# UnidadDeControl-STM.net
KiCad netlist of a schematic drawn in Altium Designer
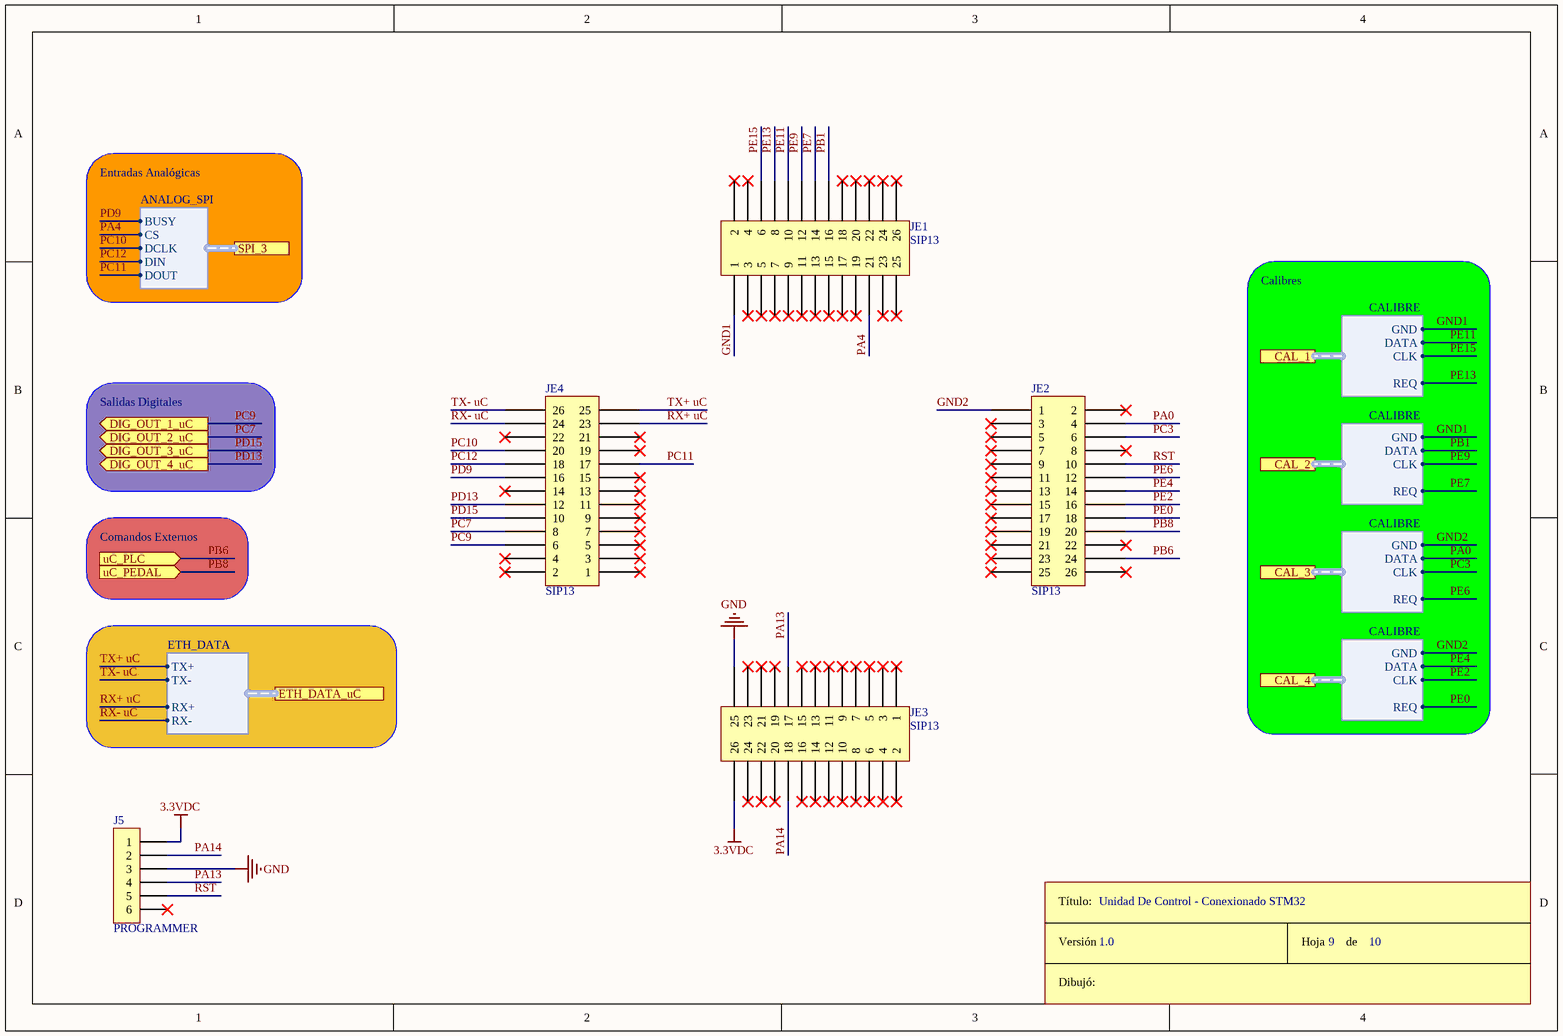
[diagram p0: UnidadDeControl-STM.SchDoc]

(export (version "E")
  (design (tool "Eeschema 10.0.6"))
  (components
    (comp (ref "J5") (value "PROGRAMMER") (footprint "SIP6") (libsource (lib "LIBEBAL") (part "CON6")))
    (comp (ref "JE1")
      (value "SIP13")
      (footprint "SIP13*2 - HDR")
      (libsource (lib "AditionalComponents") (part "CON13*2"))
    )
    (comp (ref "JE2") (value "SIP13") (footprint "SIP13*2 - HDR") (libsource (lib "") (part "CON13*2_3")))
    (comp (ref "JE3") (value "SIP13") (footprint "SIP13*2 - HDR") (libsource (lib "") (part "CON13*2_1")))
    (comp (ref "JE4") (value "SIP13") (footprint "SIP13*2 - HDR") (libsource (lib "") (part "CON13*2_2")))
    (comp (ref "ROT8") (value "Rótulo") (libsource (lib "LIB PIO IX") (part "Rótulo")))
  )
  (nets
    (net (code "4") (name "/GND1") (class "Default")
      (node (ref "JE1") (pin "1") (pinfunction "1_1") (pintype "passive"))
    )
    (net (code "5") (name "/GND2") (class "Default")
      (node (ref "JE2") (pin "1") (pinfunction "1_1") (pintype "passive"))
    )
    (net (code "6") (name "/PA0") (class "Default")
      (node (ref "JE2") (pin "4") (pinfunction "4_4") (pintype "passive"))
    )
    (net (code "7") (name "/PA4") (class "Default")
      (node (ref "JE1") (pin "21") (pinfunction "21_21") (pintype "passive"))
    )
    (net (code "8") (name "/PA13") (class "Default")
      (node (ref "J5") (pin "4") (pinfunction "4_4") (pintype "passive"))
      (node (ref "JE3") (pin "17") (pinfunction "17_17") (pintype "passive"))
    )
    (net (code "9") (name "/PA14") (class "Default")
      (node (ref "J5") (pin "2") (pinfunction "2_2") (pintype "passive"))
      (node (ref "JE3") (pin "18") (pinfunction "18_18") (pintype "passive"))
    )
    (net (code "10") (name "/PB1") (class "Default")
      (node (ref "JE1") (pin "16") (pinfunction "16_16") (pintype "passive"))
    )
    (net (code "11") (name "/PB6") (class "Default")
      (node (ref "JE2") (pin "24") (pinfunction "24_24") (pintype "passive"))
    )
    (net (code "12") (name "/PB8") (class "Default")
      (node (ref "JE2") (pin "20") (pinfunction "20_20") (pintype "passive"))
    )
    (net (code "13") (name "/PC3") (class "Default")
      (node (ref "JE2") (pin "6") (pinfunction "6_6") (pintype "passive"))
    )
    (net (code "14") (name "/PC7") (class "Default")
      (node (ref "JE4") (pin "8") (pinfunction "8_8") (pintype "passive"))
    )
    (net (code "15") (name "/PC9") (class "Default")
      (node (ref "JE4") (pin "6") (pinfunction "6_6") (pintype "passive"))
    )
    (net (code "16") (name "/PC10") (class "Default")
      (node (ref "JE4") (pin "20") (pinfunction "20_20") (pintype "passive"))
    )
    (net (code "17") (name "/PC11") (class "Default")
      (node (ref "JE4") (pin "17") (pinfunction "17_17") (pintype "passive"))
    )
    (net (code "18") (name "/PC12") (class "Default")
      (node (ref "JE4") (pin "18") (pinfunction "18_18") (pintype "passive"))
    )
    (net (code "19") (name "/PD9") (class "Default")
      (node (ref "JE4") (pin "16") (pinfunction "16_16") (pintype "passive"))
    )
    (net (code "20") (name "/PD13") (class "Default")
      (node (ref "JE4") (pin "12") (pinfunction "12_12") (pintype "passive"))
    )
    (net (code "21") (name "/PD15") (class "Default")
      (node (ref "JE4") (pin "10") (pinfunction "10_10") (pintype "passive"))
    )
    (net (code "22") (name "/PE0") (class "Default")
      (node (ref "JE2") (pin "18") (pinfunction "18_18") (pintype "passive"))
    )
    (net (code "23") (name "/PE2") (class "Default")
      (node (ref "JE2") (pin "16") (pinfunction "16_16") (pintype "passive"))
    )
    (net (code "24") (name "/PE4") (class "Default")
      (node (ref "JE2") (pin "14") (pinfunction "14_14") (pintype "passive"))
    )
    (net (code "25") (name "/PE6") (class "Default")
      (node (ref "JE2") (pin "12") (pinfunction "12_12") (pintype "passive"))
    )
    (net (code "26") (name "/PE7") (class "Default")
      (node (ref "JE1") (pin "14") (pinfunction "14_14") (pintype "passive"))
    )
    (net (code "27") (name "/PE9") (class "Default")
      (node (ref "JE1") (pin "12") (pinfunction "12_12") (pintype "passive"))
    )
    (net (code "28") (name "/PE11") (class "Default")
      (node (ref "JE1") (pin "10") (pinfunction "10_10") (pintype "passive"))
    )
    (net (code "29") (name "/PE13") (class "Default")
      (node (ref "JE1") (pin "8") (pinfunction "8_8") (pintype "passive"))
    )
    (net (code "30") (name "/PE15") (class "Default")
      (node (ref "JE1") (pin "6") (pinfunction "6_6") (pintype "passive"))
    )
    (net (code "31") (name "/RST") (class "Default")
      (node (ref "J5") (pin "5") (pinfunction "5_5") (pintype "passive"))
      (node (ref "JE2") (pin "10") (pinfunction "10_10") (pintype "passive"))
    )
    (net (code "32") (name "/RX+ uC") (class "Default")
      (node (ref "JE4") (pin "23") (pinfunction "23_23") (pintype "passive"))
    )
    (net (code "33") (name "/RX- uC") (class "Default")
      (node (ref "JE4") (pin "24") (pinfunction "24_24") (pintype "passive"))
    )
    (net (code "34") (name "/TX+ uC") (class "Default")
      (node (ref "JE4") (pin "25") (pinfunction "25_25") (pintype "passive"))
    )
    (net (code "35") (name "/TX- uC") (class "Default")
      (node (ref "JE4") (pin "26") (pinfunction "26_26") (pintype "passive"))
    )
    (net (code "39") (name "3.3VDC") (class "Default")
      (node (ref "J5") (pin "1") (pinfunction "1_1") (pintype "passive"))
      (node (ref "JE3") (pin "26") (pinfunction "26_26") (pintype "passive"))
    )
    (net (code "40") (name "GND") (class "Default")
      (node (ref "J5") (pin "3") (pinfunction "3_3") (pintype "passive"))
      (node (ref "JE3") (pin "25") (pinfunction "25_25") (pintype "passive"))
    )
    (net (code "41") (name "unconnected-(J5-Pad6)") (class "Default")
      (node (ref "J5") (pin "6") (pinfunction "6_6") (pintype "passive+no_connect"))
    )
    (net (code "42") (name "unconnected-(JE1-Pad2)") (class "Default")
      (node (ref "JE1") (pin "2") (pinfunction "2_2") (pintype "passive+no_connect"))
    )
    (net (code "43") (name "unconnected-(JE1-Pad3)") (class "Default")
      (node (ref "JE1") (pin "3") (pinfunction "3_3") (pintype "passive+no_connect"))
    )
    (net (code "44") (name "unconnected-(JE1-Pad4)") (class "Default")
      (node (ref "JE1") (pin "4") (pinfunction "4_4") (pintype "passive+no_connect"))
    )
    (net (code "45") (name "unconnected-(JE1-Pad5)") (class "Default")
      (node (ref "JE1") (pin "5") (pinfunction "5_5") (pintype "passive+no_connect"))
    )
    (net (code "46") (name "unconnected-(JE1-Pad7)") (class "Default")
      (node (ref "JE1") (pin "7") (pinfunction "7_7") (pintype "passive+no_connect"))
    )
    (net (code "47") (name "unconnected-(JE1-Pad9)") (class "Default")
      (node (ref "JE1") (pin "9") (pinfunction "9_9") (pintype "passive+no_connect"))
    )
    (net (code "48") (name "unconnected-(JE1-Pad11)") (class "Default")
      (node (ref "JE1") (pin "11") (pinfunction "11_11") (pintype "passive+no_connect"))
    )
    (net (code "49") (name "unconnected-(JE1-Pad13)") (class "Default")
      (node (ref "JE1") (pin "13") (pinfunction "13_13") (pintype "passive+no_connect"))
    )
    (net (code "50") (name "unconnected-(JE1-Pad15)") (class "Default")
      (node (ref "JE1") (pin "15") (pinfunction "15_15") (pintype "passive+no_connect"))
    )
    (net (code "51") (name "unconnected-(JE1-Pad17)") (class "Default")
      (node (ref "JE1") (pin "17") (pinfunction "17_17") (pintype "passive+no_connect"))
    )
    (net (code "52") (name "unconnected-(JE1-Pad18)") (class "Default")
      (node (ref "JE1") (pin "18") (pinfunction "18_18") (pintype "passive+no_connect"))
    )
    (net (code "53") (name "unconnected-(JE1-Pad19)") (class "Default")
      (node (ref "JE1") (pin "19") (pinfunction "19_19") (pintype "passive+no_connect"))
    )
    (net (code "54") (name "unconnected-(JE1-Pad20)") (class "Default")
      (node (ref "JE1") (pin "20") (pinfunction "20_20") (pintype "passive+no_connect"))
    )
    (net (code "55") (name "unconnected-(JE1-Pad22)") (class "Default")
      (node (ref "JE1") (pin "22") (pinfunction "22_22") (pintype "passive+no_connect"))
    )
    (net (code "56") (name "unconnected-(JE1-Pad23)") (class "Default")
      (node (ref "JE1") (pin "23") (pinfunction "23_23") (pintype "passive+no_connect"))
    )
    (net (code "57") (name "unconnected-(JE1-Pad24)") (class "Default")
      (node (ref "JE1") (pin "24") (pinfunction "24_24") (pintype "passive+no_connect"))
    )
    (net (code "58") (name "unconnected-(JE1-Pad25)") (class "Default")
      (node (ref "JE1") (pin "25") (pinfunction "25_25") (pintype "passive+no_connect"))
    )
    (net (code "59") (name "unconnected-(JE1-Pad26)") (class "Default")
      (node (ref "JE1") (pin "26") (pinfunction "26_26") (pintype "passive+no_connect"))
    )
    (net (code "60") (name "unconnected-(JE2-Pad2)") (class "Default")
      (node (ref "JE2") (pin "2") (pinfunction "2_2") (pintype "passive+no_connect"))
    )
    (net (code "61") (name "unconnected-(JE2-Pad3)") (class "Default")
      (node (ref "JE2") (pin "3") (pinfunction "3_3") (pintype "passive+no_connect"))
    )
    (net (code "62") (name "unconnected-(JE2-Pad5)") (class "Default")
      (node (ref "JE2") (pin "5") (pinfunction "5_5") (pintype "passive+no_connect"))
    )
    (net (code "63") (name "unconnected-(JE2-Pad7)") (class "Default")
      (node (ref "JE2") (pin "7") (pinfunction "7_7") (pintype "passive+no_connect"))
    )
    (net (code "64") (name "unconnected-(JE2-Pad8)") (class "Default")
      (node (ref "JE2") (pin "8") (pinfunction "8_8") (pintype "passive+no_connect"))
    )
    (net (code "65") (name "unconnected-(JE2-Pad9)") (class "Default")
      (node (ref "JE2") (pin "9") (pinfunction "9_9") (pintype "passive+no_connect"))
    )
    (net (code "66") (name "unconnected-(JE2-Pad11)") (class "Default")
      (node (ref "JE2") (pin "11") (pinfunction "11_11") (pintype "passive+no_connect"))
    )
    (net (code "67") (name "unconnected-(JE2-Pad13)") (class "Default")
      (node (ref "JE2") (pin "13") (pinfunction "13_13") (pintype "passive+no_connect"))
    )
    (net (code "68") (name "unconnected-(JE2-Pad15)") (class "Default")
      (node (ref "JE2") (pin "15") (pinfunction "15_15") (pintype "passive+no_connect"))
    )
    (net (code "69") (name "unconnected-(JE2-Pad17)") (class "Default")
      (node (ref "JE2") (pin "17") (pinfunction "17_17") (pintype "passive+no_connect"))
    )
    (net (code "70") (name "unconnected-(JE2-Pad19)") (class "Default")
      (node (ref "JE2") (pin "19") (pinfunction "19_19") (pintype "passive+no_connect"))
    )
    (net (code "71") (name "unconnected-(JE2-Pad21)") (class "Default")
      (node (ref "JE2") (pin "21") (pinfunction "21_21") (pintype "passive+no_connect"))
    )
    (net (code "72") (name "unconnected-(JE2-Pad22)") (class "Default")
      (node (ref "JE2") (pin "22") (pinfunction "22_22") (pintype "passive+no_connect"))
    )
    (net (code "73") (name "unconnected-(JE2-Pad23)") (class "Default")
      (node (ref "JE2") (pin "23") (pinfunction "23_23") (pintype "passive+no_connect"))
    )
    (net (code "74") (name "unconnected-(JE2-Pad25)") (class "Default")
      (node (ref "JE2") (pin "25") (pinfunction "25_25") (pintype "passive+no_connect"))
    )
    (net (code "75") (name "unconnected-(JE2-Pad26)") (class "Default")
      (node (ref "JE2") (pin "26") (pinfunction "26_26") (pintype "passive+no_connect"))
    )
    (net (code "76") (name "unconnected-(JE3-Pad1)") (class "Default")
      (node (ref "JE3") (pin "1") (pinfunction "1_1") (pintype "passive+no_connect"))
    )
    (net (code "77") (name "unconnected-(JE3-Pad2)") (class "Default")
      (node (ref "JE3") (pin "2") (pinfunction "2_2") (pintype "passive+no_connect"))
    )
    (net (code "78") (name "unconnected-(JE3-Pad3)") (class "Default")
      (node (ref "JE3") (pin "3") (pinfunction "3_3") (pintype "passive+no_connect"))
    )
    (net (code "79") (name "unconnected-(JE3-Pad4)") (class "Default")
      (node (ref "JE3") (pin "4") (pinfunction "4_4") (pintype "passive+no_connect"))
    )
    (net (code "80") (name "unconnected-(JE3-Pad5)") (class "Default")
      (node (ref "JE3") (pin "5") (pinfunction "5_5") (pintype "passive+no_connect"))
    )
    (net (code "81") (name "unconnected-(JE3-Pad6)") (class "Default")
      (node (ref "JE3") (pin "6") (pinfunction "6_6") (pintype "passive+no_connect"))
    )
    (net (code "82") (name "unconnected-(JE3-Pad7)") (class "Default")
      (node (ref "JE3") (pin "7") (pinfunction "7_7") (pintype "passive+no_connect"))
    )
    (net (code "83") (name "unconnected-(JE3-Pad8)") (class "Default")
      (node (ref "JE3") (pin "8") (pinfunction "8_8") (pintype "passive+no_connect"))
    )
    (net (code "84") (name "unconnected-(JE3-Pad9)") (class "Default")
      (node (ref "JE3") (pin "9") (pinfunction "9_9") (pintype "passive+no_connect"))
    )
    (net (code "85") (name "unconnected-(JE3-Pad10)") (class "Default")
      (node (ref "JE3") (pin "10") (pinfunction "10_10") (pintype "passive+no_connect"))
    )
    (net (code "86") (name "unconnected-(JE3-Pad11)") (class "Default")
      (node (ref "JE3") (pin "11") (pinfunction "11_11") (pintype "passive+no_connect"))
    )
    (net (code "87") (name "unconnected-(JE3-Pad12)") (class "Default")
      (node (ref "JE3") (pin "12") (pinfunction "12_12") (pintype "passive+no_connect"))
    )
    (net (code "88") (name "unconnected-(JE3-Pad13)") (class "Default")
      (node (ref "JE3") (pin "13") (pinfunction "13_13") (pintype "passive+no_connect"))
    )
    (net (code "89") (name "unconnected-(JE3-Pad14)") (class "Default")
      (node (ref "JE3") (pin "14") (pinfunction "14_14") (pintype "passive+no_connect"))
    )
    (net (code "90") (name "unconnected-(JE3-Pad15)") (class "Default")
      (node (ref "JE3") (pin "15") (pinfunction "15_15") (pintype "passive+no_connect"))
    )
    (net (code "91") (name "unconnected-(JE3-Pad16)") (class "Default")
      (node (ref "JE3") (pin "16") (pinfunction "16_16") (pintype "passive+no_connect"))
    )
    (net (code "92") (name "unconnected-(JE3-Pad19)") (class "Default")
      (node (ref "JE3") (pin "19") (pinfunction "19_19") (pintype "passive+no_connect"))
    )
    (net (code "93") (name "unconnected-(JE3-Pad20)") (class "Default")
      (node (ref "JE3") (pin "20") (pinfunction "20_20") (pintype "passive+no_connect"))
    )
    (net (code "94") (name "unconnected-(JE3-Pad21)") (class "Default")
      (node (ref "JE3") (pin "21") (pinfunction "21_21") (pintype "passive+no_connect"))
    )
    (net (code "95") (name "unconnected-(JE3-Pad22)") (class "Default")
      (node (ref "JE3") (pin "22") (pinfunction "22_22") (pintype "passive+no_connect"))
    )
    (net (code "96") (name "unconnected-(JE3-Pad23)") (class "Default")
      (node (ref "JE3") (pin "23") (pinfunction "23_23") (pintype "passive+no_connect"))
    )
    (net (code "97") (name "unconnected-(JE3-Pad24)") (class "Default")
      (node (ref "JE3") (pin "24") (pinfunction "24_24") (pintype "passive+no_connect"))
    )
    (net (code "98") (name "unconnected-(JE4-Pad1)") (class "Default")
      (node (ref "JE4") (pin "1") (pinfunction "1_1") (pintype "passive+no_connect"))
    )
    (net (code "99") (name "unconnected-(JE4-Pad2)") (class "Default")
      (node (ref "JE4") (pin "2") (pinfunction "2_2") (pintype "passive+no_connect"))
    )
    (net (code "100") (name "unconnected-(JE4-Pad3)") (class "Default")
      (node (ref "JE4") (pin "3") (pinfunction "3_3") (pintype "passive+no_connect"))
    )
    (net (code "101") (name "unconnected-(JE4-Pad4)") (class "Default")
      (node (ref "JE4") (pin "4") (pinfunction "4_4") (pintype "passive+no_connect"))
    )
    (net (code "102") (name "unconnected-(JE4-Pad5)") (class "Default")
      (node (ref "JE4") (pin "5") (pinfunction "5_5") (pintype "passive+no_connect"))
    )
    (net (code "103") (name "unconnected-(JE4-Pad7)") (class "Default")
      (node (ref "JE4") (pin "7") (pinfunction "7_7") (pintype "passive+no_connect"))
    )
    (net (code "104") (name "unconnected-(JE4-Pad9)") (class "Default")
      (node (ref "JE4") (pin "9") (pinfunction "9_9") (pintype "passive+no_connect"))
    )
    (net (code "105") (name "unconnected-(JE4-Pad11)") (class "Default")
      (node (ref "JE4") (pin "11") (pinfunction "11_11") (pintype "passive+no_connect"))
    )
    (net (code "106") (name "unconnected-(JE4-Pad13)") (class "Default")
      (node (ref "JE4") (pin "13") (pinfunction "13_13") (pintype "passive+no_connect"))
    )
    (net (code "107") (name "unconnected-(JE4-Pad14)") (class "Default")
      (node (ref "JE4") (pin "14") (pinfunction "14_14") (pintype "passive+no_connect"))
    )
    (net (code "108") (name "unconnected-(JE4-Pad15)") (class "Default")
      (node (ref "JE4") (pin "15") (pinfunction "15_15") (pintype "passive+no_connect"))
    )
    (net (code "109") (name "unconnected-(JE4-Pad19)") (class "Default")
      (node (ref "JE4") (pin "19") (pinfunction "19_19") (pintype "passive+no_connect"))
    )
    (net (code "110") (name "unconnected-(JE4-Pad21)") (class "Default")
      (node (ref "JE4") (pin "21") (pinfunction "21_21") (pintype "passive+no_connect"))
    )
    (net (code "111") (name "unconnected-(JE4-Pad22)") (class "Default")
      (node (ref "JE4") (pin "22") (pinfunction "22_22") (pintype "passive+no_connect"))
    )
  )
)
